# v1.net
KiCad netlist of a schematic drawn in EAGLE
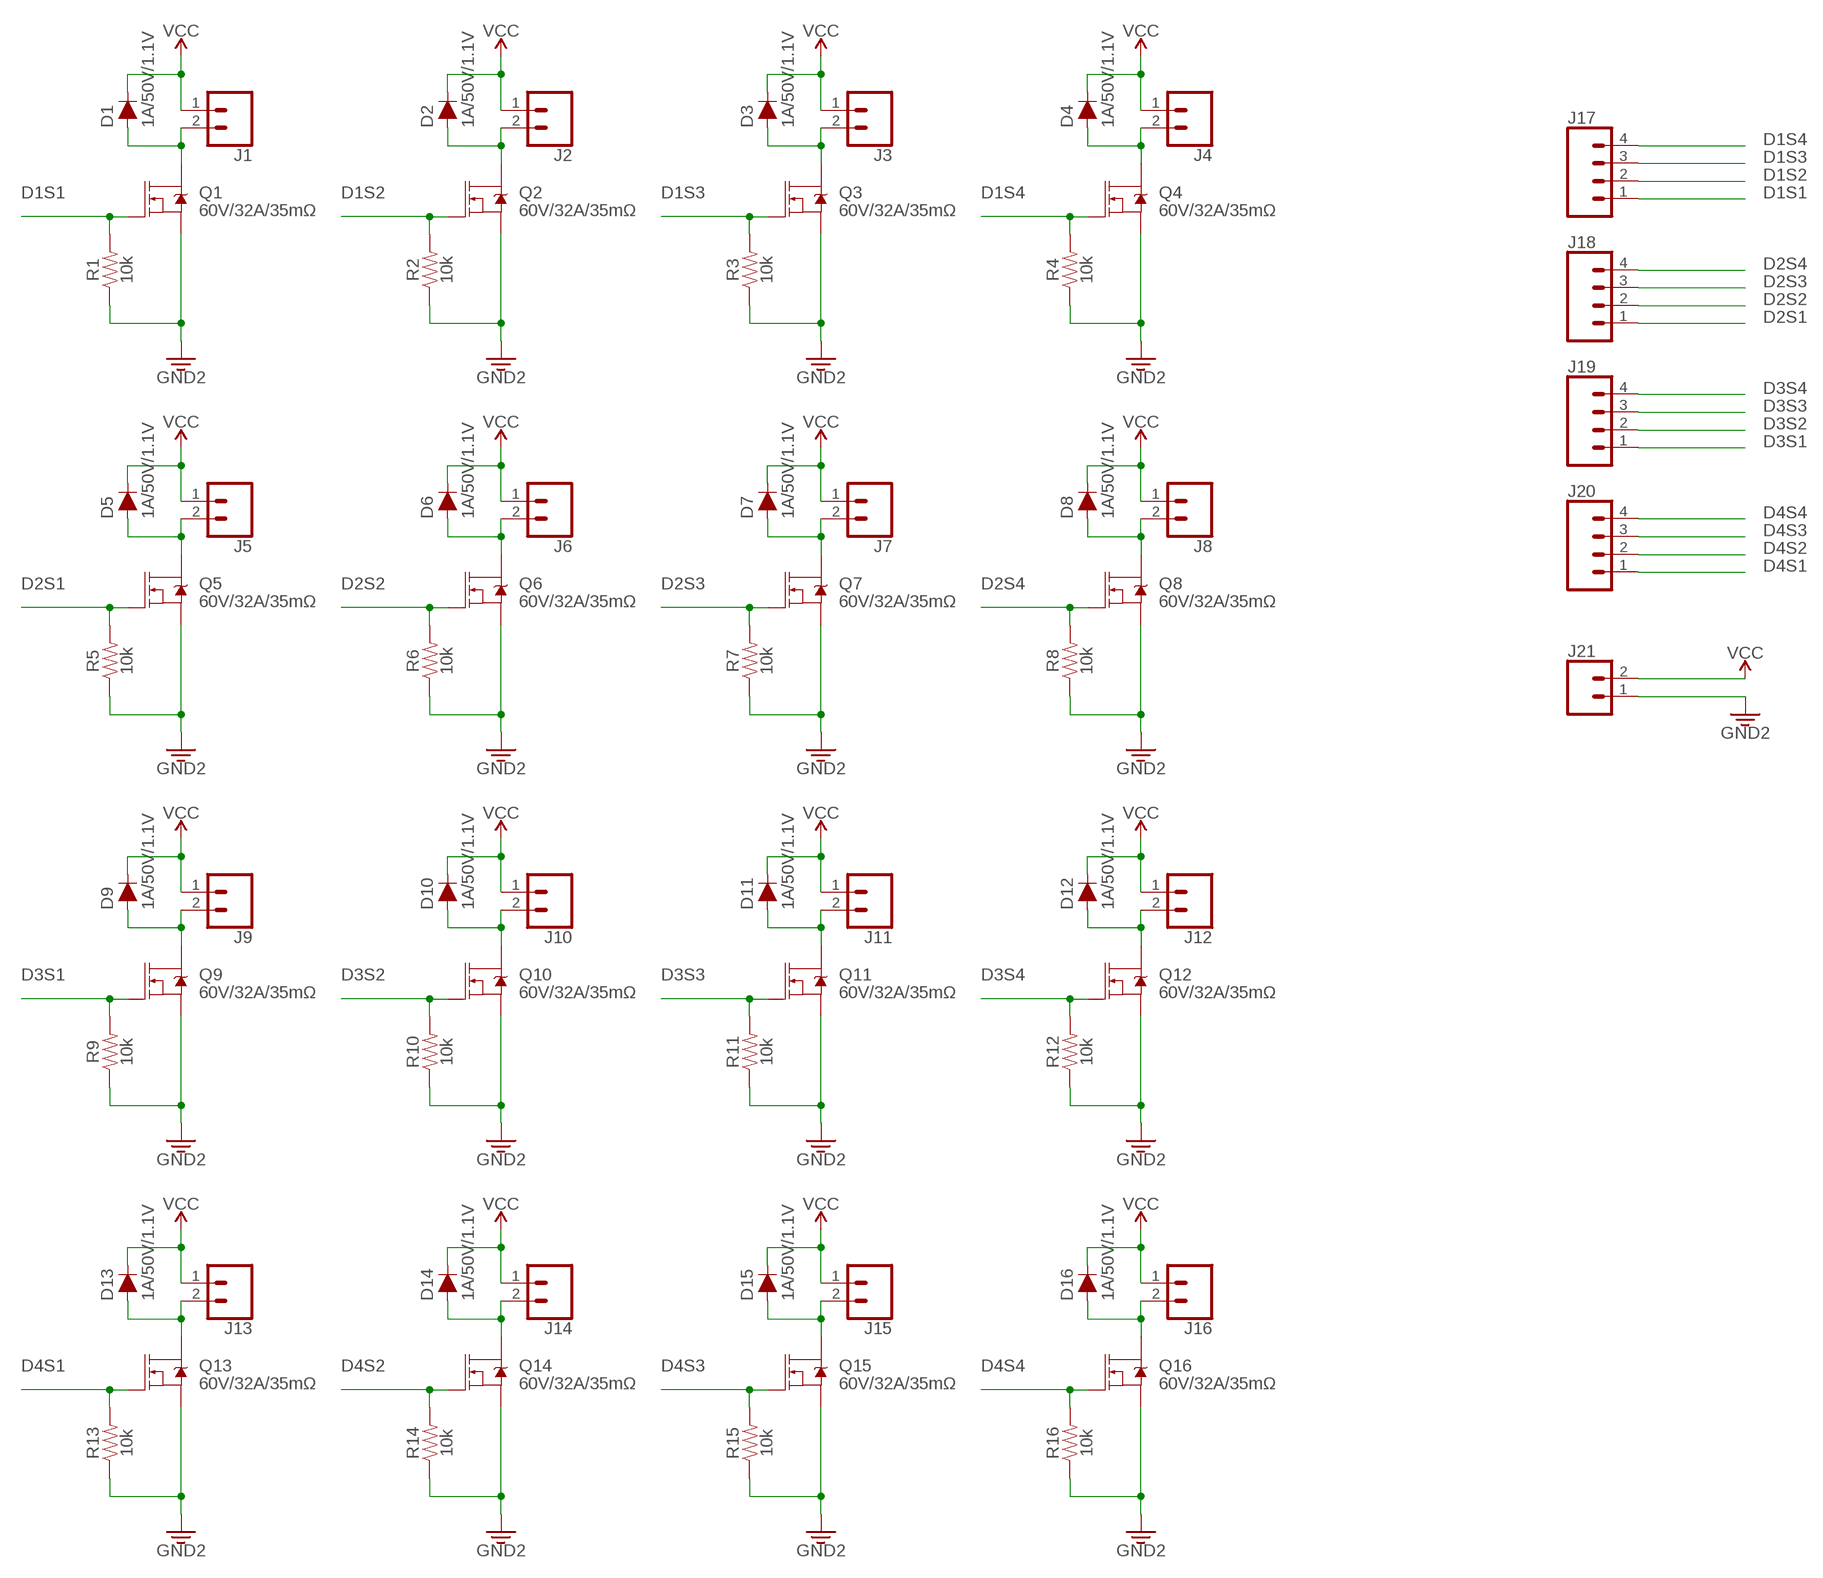
[diagram p0: schematic, sheet 1]

(export (version "E")
  (design (tool "Eeschema 10.0.6"))
  (components
    (comp (ref "D1")
      (value "1A/50V/1.1V")
      (footprint "eagle-import:DIODE-1N4001")
      (libsource (lib "eagle-import") (part "DIODE-PTH"))
    )
    (comp (ref "D2")
      (value "1A/50V/1.1V")
      (footprint "eagle-import:DIODE-1N4001")
      (libsource (lib "eagle-import") (part "DIODE-PTH"))
    )
    (comp (ref "D3")
      (value "1A/50V/1.1V")
      (footprint "eagle-import:DIODE-1N4001")
      (libsource (lib "eagle-import") (part "DIODE-PTH"))
    )
    (comp (ref "D4")
      (value "1A/50V/1.1V")
      (footprint "eagle-import:DIODE-1N4001")
      (libsource (lib "eagle-import") (part "DIODE-PTH"))
    )
    (comp (ref "D5")
      (value "1A/50V/1.1V")
      (footprint "eagle-import:DIODE-1N4001")
      (libsource (lib "eagle-import") (part "DIODE-PTH"))
    )
    (comp (ref "D6")
      (value "1A/50V/1.1V")
      (footprint "eagle-import:DIODE-1N4001")
      (libsource (lib "eagle-import") (part "DIODE-PTH"))
    )
    (comp (ref "D7")
      (value "1A/50V/1.1V")
      (footprint "eagle-import:DIODE-1N4001")
      (libsource (lib "eagle-import") (part "DIODE-PTH"))
    )
    (comp (ref "D8")
      (value "1A/50V/1.1V")
      (footprint "eagle-import:DIODE-1N4001")
      (libsource (lib "eagle-import") (part "DIODE-PTH"))
    )
    (comp (ref "D9")
      (value "1A/50V/1.1V")
      (footprint "eagle-import:DIODE-1N4001")
      (libsource (lib "eagle-import") (part "DIODE-PTH"))
    )
    (comp (ref "D10")
      (value "1A/50V/1.1V")
      (footprint "eagle-import:DIODE-1N4001")
      (libsource (lib "eagle-import") (part "DIODE-PTH"))
    )
    (comp (ref "D11")
      (value "1A/50V/1.1V")
      (footprint "eagle-import:DIODE-1N4001")
      (libsource (lib "eagle-import") (part "DIODE-PTH"))
    )
    (comp (ref "D12")
      (value "1A/50V/1.1V")
      (footprint "eagle-import:DIODE-1N4001")
      (libsource (lib "eagle-import") (part "DIODE-PTH"))
    )
    (comp (ref "D13")
      (value "1A/50V/1.1V")
      (footprint "eagle-import:DIODE-1N4001")
      (libsource (lib "eagle-import") (part "DIODE-PTH"))
    )
    (comp (ref "D14")
      (value "1A/50V/1.1V")
      (footprint "eagle-import:DIODE-1N4001")
      (libsource (lib "eagle-import") (part "DIODE-PTH"))
    )
    (comp (ref "D15")
      (value "1A/50V/1.1V")
      (footprint "eagle-import:DIODE-1N4001")
      (libsource (lib "eagle-import") (part "DIODE-PTH"))
    )
    (comp (ref "D16")
      (value "1A/50V/1.1V")
      (footprint "eagle-import:DIODE-1N4001")
      (libsource (lib "eagle-import") (part "DIODE-PTH"))
    )
    (comp (ref "J1")
      (value "CONN_02")
      (footprint "eagle-import:1X02")
      (libsource (lib "eagle-import") (part "CONN_02"))
    )
    (comp (ref "J2")
      (value "CONN_02")
      (footprint "eagle-import:1X02")
      (libsource (lib "eagle-import") (part "CONN_02"))
    )
    (comp (ref "J3")
      (value "CONN_02")
      (footprint "eagle-import:1X02")
      (libsource (lib "eagle-import") (part "CONN_02"))
    )
    (comp (ref "J4")
      (value "CONN_02")
      (footprint "eagle-import:1X02")
      (libsource (lib "eagle-import") (part "CONN_02"))
    )
    (comp (ref "J5")
      (value "CONN_02")
      (footprint "eagle-import:1X02")
      (libsource (lib "eagle-import") (part "CONN_02"))
    )
    (comp (ref "J6")
      (value "CONN_02")
      (footprint "eagle-import:1X02")
      (libsource (lib "eagle-import") (part "CONN_02"))
    )
    (comp (ref "J7")
      (value "CONN_02")
      (footprint "eagle-import:1X02")
      (libsource (lib "eagle-import") (part "CONN_02"))
    )
    (comp (ref "J8")
      (value "CONN_02")
      (footprint "eagle-import:1X02")
      (libsource (lib "eagle-import") (part "CONN_02"))
    )
    (comp (ref "J9")
      (value "CONN_02")
      (footprint "eagle-import:1X02")
      (libsource (lib "eagle-import") (part "CONN_02"))
    )
    (comp (ref "J10")
      (value "CONN_02")
      (footprint "eagle-import:1X02")
      (libsource (lib "eagle-import") (part "CONN_02"))
    )
    (comp (ref "J11")
      (value "CONN_02")
      (footprint "eagle-import:1X02")
      (libsource (lib "eagle-import") (part "CONN_02"))
    )
    (comp (ref "J12")
      (value "CONN_02")
      (footprint "eagle-import:1X02")
      (libsource (lib "eagle-import") (part "CONN_02"))
    )
    (comp (ref "J13")
      (value "CONN_02")
      (footprint "eagle-import:1X02")
      (libsource (lib "eagle-import") (part "CONN_02"))
    )
    (comp (ref "J14")
      (value "CONN_02")
      (footprint "eagle-import:1X02")
      (libsource (lib "eagle-import") (part "CONN_02"))
    )
    (comp (ref "J15")
      (value "CONN_02")
      (footprint "eagle-import:1X02")
      (libsource (lib "eagle-import") (part "CONN_02"))
    )
    (comp (ref "J16")
      (value "CONN_02")
      (footprint "eagle-import:1X02")
      (libsource (lib "eagle-import") (part "CONN_02"))
    )
    (comp (ref "J17")
      (value "CONN_04JST-PTH-VERT")
      (footprint "eagle-import:JST-4-PTH-VERT")
      (libsource (lib "eagle-import") (part "CONN_04JST-PTH-VERT"))
    )
    (comp (ref "J18")
      (value "CONN_04JST-PTH-VERT")
      (footprint "eagle-import:JST-4-PTH-VERT")
      (libsource (lib "eagle-import") (part "CONN_04JST-PTH-VERT"))
    )
    (comp (ref "J19")
      (value "CONN_04JST-PTH-VERT")
      (footprint "eagle-import:JST-4-PTH-VERT")
      (libsource (lib "eagle-import") (part "CONN_04JST-PTH-VERT"))
    )
    (comp (ref "J20")
      (value "CONN_04JST-PTH-VERT")
      (footprint "eagle-import:JST-4-PTH-VERT")
      (libsource (lib "eagle-import") (part "CONN_04JST-PTH-VERT"))
    )
    (comp (ref "J21")
      (value "CONN_025MM")
      (footprint "eagle-import:SCREWTERMINAL-5MM-2")
      (libsource (lib "eagle-import") (part "CONN_025MM"))
    )
    (comp (ref "Q1")
      (value "60V/32A/35mΩ")
      (footprint "eagle-import:TO220V")
      (libsource (lib "eagle-import") (part "MOSFET-NCH-FQP30N06L"))
    )
    (comp (ref "Q2")
      (value "60V/32A/35mΩ")
      (footprint "eagle-import:TO220V")
      (libsource (lib "eagle-import") (part "MOSFET-NCH-FQP30N06L"))
    )
    (comp (ref "Q3")
      (value "60V/32A/35mΩ")
      (footprint "eagle-import:TO220V")
      (libsource (lib "eagle-import") (part "MOSFET-NCH-FQP30N06L"))
    )
    (comp (ref "Q4")
      (value "60V/32A/35mΩ")
      (footprint "eagle-import:TO220V")
      (libsource (lib "eagle-import") (part "MOSFET-NCH-FQP30N06L"))
    )
    (comp (ref "Q5")
      (value "60V/32A/35mΩ")
      (footprint "eagle-import:TO220V")
      (libsource (lib "eagle-import") (part "MOSFET-NCH-FQP30N06L"))
    )
    (comp (ref "Q6")
      (value "60V/32A/35mΩ")
      (footprint "eagle-import:TO220V")
      (libsource (lib "eagle-import") (part "MOSFET-NCH-FQP30N06L"))
    )
    (comp (ref "Q7")
      (value "60V/32A/35mΩ")
      (footprint "eagle-import:TO220V")
      (libsource (lib "eagle-import") (part "MOSFET-NCH-FQP30N06L"))
    )
    (comp (ref "Q8")
      (value "60V/32A/35mΩ")
      (footprint "eagle-import:TO220V")
      (libsource (lib "eagle-import") (part "MOSFET-NCH-FQP30N06L"))
    )
    (comp (ref "Q9")
      (value "60V/32A/35mΩ")
      (footprint "eagle-import:TO220V")
      (libsource (lib "eagle-import") (part "MOSFET-NCH-FQP30N06L"))
    )
    (comp (ref "Q10")
      (value "60V/32A/35mΩ")
      (footprint "eagle-import:TO220V")
      (libsource (lib "eagle-import") (part "MOSFET-NCH-FQP30N06L"))
    )
    (comp (ref "Q11")
      (value "60V/32A/35mΩ")
      (footprint "eagle-import:TO220V")
      (libsource (lib "eagle-import") (part "MOSFET-NCH-FQP30N06L"))
    )
    (comp (ref "Q12")
      (value "60V/32A/35mΩ")
      (footprint "eagle-import:TO220V")
      (libsource (lib "eagle-import") (part "MOSFET-NCH-FQP30N06L"))
    )
    (comp (ref "Q13")
      (value "60V/32A/35mΩ")
      (footprint "eagle-import:TO220V")
      (libsource (lib "eagle-import") (part "MOSFET-NCH-FQP30N06L"))
    )
    (comp (ref "Q14")
      (value "60V/32A/35mΩ")
      (footprint "eagle-import:TO220V")
      (libsource (lib "eagle-import") (part "MOSFET-NCH-FQP30N06L"))
    )
    (comp (ref "Q15")
      (value "60V/32A/35mΩ")
      (footprint "eagle-import:TO220V")
      (libsource (lib "eagle-import") (part "MOSFET-NCH-FQP30N06L"))
    )
    (comp (ref "Q16")
      (value "60V/32A/35mΩ")
      (footprint "eagle-import:TO220V")
      (libsource (lib "eagle-import") (part "MOSFET-NCH-FQP30N06L"))
    )
    (comp (ref "R1")
      (value "10k")
      (footprint "eagle-import:AXIAL-0.3-KIT")
      (libsource (lib "eagle-import") (part "10KOHM-HORIZ_KIT-1/4W-5%"))
    )
    (comp (ref "R2")
      (value "10k")
      (footprint "eagle-import:AXIAL-0.3-KIT")
      (libsource (lib "eagle-import") (part "10KOHM-HORIZ_KIT-1/4W-5%"))
    )
    (comp (ref "R3")
      (value "10k")
      (footprint "eagle-import:AXIAL-0.3-KIT")
      (libsource (lib "eagle-import") (part "10KOHM-HORIZ_KIT-1/4W-5%"))
    )
    (comp (ref "R4")
      (value "10k")
      (footprint "eagle-import:AXIAL-0.3-KIT")
      (libsource (lib "eagle-import") (part "10KOHM-HORIZ_KIT-1/4W-5%"))
    )
    (comp (ref "R5")
      (value "10k")
      (footprint "eagle-import:AXIAL-0.3-KIT")
      (libsource (lib "eagle-import") (part "10KOHM-HORIZ_KIT-1/4W-5%"))
    )
    (comp (ref "R6")
      (value "10k")
      (footprint "eagle-import:AXIAL-0.3-KIT")
      (libsource (lib "eagle-import") (part "10KOHM-HORIZ_KIT-1/4W-5%"))
    )
    (comp (ref "R7")
      (value "10k")
      (footprint "eagle-import:AXIAL-0.3-KIT")
      (libsource (lib "eagle-import") (part "10KOHM-HORIZ_KIT-1/4W-5%"))
    )
    (comp (ref "R8")
      (value "10k")
      (footprint "eagle-import:AXIAL-0.3-KIT")
      (libsource (lib "eagle-import") (part "10KOHM-HORIZ_KIT-1/4W-5%"))
    )
    (comp (ref "R9")
      (value "10k")
      (footprint "eagle-import:AXIAL-0.3-KIT")
      (libsource (lib "eagle-import") (part "10KOHM-HORIZ_KIT-1/4W-5%"))
    )
    (comp (ref "R10")
      (value "10k")
      (footprint "eagle-import:AXIAL-0.3-KIT")
      (libsource (lib "eagle-import") (part "10KOHM-HORIZ_KIT-1/4W-5%"))
    )
    (comp (ref "R11")
      (value "10k")
      (footprint "eagle-import:AXIAL-0.3-KIT")
      (libsource (lib "eagle-import") (part "10KOHM-HORIZ_KIT-1/4W-5%"))
    )
    (comp (ref "R12")
      (value "10k")
      (footprint "eagle-import:AXIAL-0.3-KIT")
      (libsource (lib "eagle-import") (part "10KOHM-HORIZ_KIT-1/4W-5%"))
    )
    (comp (ref "R13")
      (value "10k")
      (footprint "eagle-import:AXIAL-0.3-KIT")
      (libsource (lib "eagle-import") (part "10KOHM-HORIZ_KIT-1/4W-5%"))
    )
    (comp (ref "R14")
      (value "10k")
      (footprint "eagle-import:AXIAL-0.3-KIT")
      (libsource (lib "eagle-import") (part "10KOHM-HORIZ_KIT-1/4W-5%"))
    )
    (comp (ref "R15")
      (value "10k")
      (footprint "eagle-import:AXIAL-0.3-KIT")
      (libsource (lib "eagle-import") (part "10KOHM-HORIZ_KIT-1/4W-5%"))
    )
    (comp (ref "R16")
      (value "10k")
      (footprint "eagle-import:AXIAL-0.3-KIT")
      (libsource (lib "eagle-import") (part "10KOHM-HORIZ_KIT-1/4W-5%"))
    )
  )
  (nets
    (net (code "1") (name "/D1S1") (class "Default")
      (node (ref "J17") (pin "1") (pinfunction "1_1") (pintype "passive"))
      (node (ref "Q1") (pin "1") (pinfunction "G_1") (pintype "bidirectional"))
      (node (ref "R1") (pin "P$2") (pinfunction "2_P$2") (pintype "passive"))
    )
    (net (code "2") (name "/D1S2") (class "Default")
      (node (ref "J17") (pin "2") (pinfunction "2_2") (pintype "passive"))
      (node (ref "Q2") (pin "1") (pinfunction "G_1") (pintype "bidirectional"))
      (node (ref "R2") (pin "P$2") (pinfunction "2_P$2") (pintype "passive"))
    )
    (net (code "3") (name "/D1S3") (class "Default")
      (node (ref "J17") (pin "3") (pinfunction "3_3") (pintype "passive"))
      (node (ref "Q3") (pin "1") (pinfunction "G_1") (pintype "bidirectional"))
      (node (ref "R3") (pin "P$2") (pinfunction "2_P$2") (pintype "passive"))
    )
    (net (code "4") (name "/D1S4") (class "Default")
      (node (ref "J17") (pin "4") (pinfunction "4_4") (pintype "passive"))
      (node (ref "Q4") (pin "1") (pinfunction "G_1") (pintype "bidirectional"))
      (node (ref "R4") (pin "P$2") (pinfunction "2_P$2") (pintype "passive"))
    )
    (net (code "5") (name "/D2S1") (class "Default")
      (node (ref "J18") (pin "1") (pinfunction "1_1") (pintype "passive"))
      (node (ref "Q5") (pin "1") (pinfunction "G_1") (pintype "bidirectional"))
      (node (ref "R5") (pin "P$2") (pinfunction "2_P$2") (pintype "passive"))
    )
    (net (code "6") (name "/D2S2") (class "Default")
      (node (ref "J18") (pin "2") (pinfunction "2_2") (pintype "passive"))
      (node (ref "Q6") (pin "1") (pinfunction "G_1") (pintype "bidirectional"))
      (node (ref "R6") (pin "P$2") (pinfunction "2_P$2") (pintype "passive"))
    )
    (net (code "7") (name "/D2S3") (class "Default")
      (node (ref "J18") (pin "3") (pinfunction "3_3") (pintype "passive"))
      (node (ref "Q7") (pin "1") (pinfunction "G_1") (pintype "bidirectional"))
      (node (ref "R7") (pin "P$2") (pinfunction "2_P$2") (pintype "passive"))
    )
    (net (code "8") (name "/D2S4") (class "Default")
      (node (ref "J18") (pin "4") (pinfunction "4_4") (pintype "passive"))
      (node (ref "Q8") (pin "1") (pinfunction "G_1") (pintype "bidirectional"))
      (node (ref "R8") (pin "P$2") (pinfunction "2_P$2") (pintype "passive"))
    )
    (net (code "9") (name "/D3S1") (class "Default")
      (node (ref "J19") (pin "1") (pinfunction "1_1") (pintype "passive"))
      (node (ref "Q9") (pin "1") (pinfunction "G_1") (pintype "bidirectional"))
      (node (ref "R9") (pin "P$2") (pinfunction "2_P$2") (pintype "passive"))
    )
    (net (code "10") (name "/D3S2") (class "Default")
      (node (ref "J19") (pin "2") (pinfunction "2_2") (pintype "passive"))
      (node (ref "Q10") (pin "1") (pinfunction "G_1") (pintype "bidirectional"))
      (node (ref "R10") (pin "P$2") (pinfunction "2_P$2") (pintype "passive"))
    )
    (net (code "11") (name "/D3S3") (class "Default")
      (node (ref "J19") (pin "3") (pinfunction "3_3") (pintype "passive"))
      (node (ref "Q11") (pin "1") (pinfunction "G_1") (pintype "bidirectional"))
      (node (ref "R11") (pin "P$2") (pinfunction "2_P$2") (pintype "passive"))
    )
    (net (code "12") (name "/D3S4") (class "Default")
      (node (ref "J19") (pin "4") (pinfunction "4_4") (pintype "passive"))
      (node (ref "Q12") (pin "1") (pinfunction "G_1") (pintype "bidirectional"))
      (node (ref "R12") (pin "P$2") (pinfunction "2_P$2") (pintype "passive"))
    )
    (net (code "13") (name "/D4S1") (class "Default")
      (node (ref "J20") (pin "1") (pinfunction "1_1") (pintype "passive"))
      (node (ref "Q13") (pin "1") (pinfunction "G_1") (pintype "bidirectional"))
      (node (ref "R13") (pin "P$2") (pinfunction "2_P$2") (pintype "passive"))
    )
    (net (code "14") (name "/D4S2") (class "Default")
      (node (ref "J20") (pin "2") (pinfunction "2_2") (pintype "passive"))
      (node (ref "Q14") (pin "1") (pinfunction "G_1") (pintype "bidirectional"))
      (node (ref "R14") (pin "P$2") (pinfunction "2_P$2") (pintype "passive"))
    )
    (net (code "15") (name "/D4S3") (class "Default")
      (node (ref "J20") (pin "3") (pinfunction "3_3") (pintype "passive"))
      (node (ref "Q15") (pin "1") (pinfunction "G_1") (pintype "bidirectional"))
      (node (ref "R15") (pin "P$2") (pinfunction "2_P$2") (pintype "passive"))
    )
    (net (code "16") (name "/D4S4") (class "Default")
      (node (ref "J20") (pin "4") (pinfunction "4_4") (pintype "passive"))
      (node (ref "Q16") (pin "1") (pinfunction "G_1") (pintype "bidirectional"))
      (node (ref "R16") (pin "P$2") (pinfunction "2_P$2") (pintype "passive"))
    )
    (net (code "17") (name "GND2") (class "Default")
      (node (ref "J21") (pin "1") (pinfunction "1_1") (pintype "passive"))
      (node (ref "Q1") (pin "3") (pinfunction "S_3") (pintype "bidirectional"))
      (node (ref "Q10") (pin "3") (pinfunction "S_3") (pintype "bidirectional"))
      (node (ref "Q11") (pin "3") (pinfunction "S_3") (pintype "bidirectional"))
      (node (ref "Q12") (pin "3") (pinfunction "S_3") (pintype "bidirectional"))
      (node (ref "Q13") (pin "3") (pinfunction "S_3") (pintype "bidirectional"))
      (node (ref "Q14") (pin "3") (pinfunction "S_3") (pintype "bidirectional"))
      (node (ref "Q15") (pin "3") (pinfunction "S_3") (pintype "bidirectional"))
      (node (ref "Q16") (pin "3") (pinfunction "S_3") (pintype "bidirectional"))
      (node (ref "Q2") (pin "3") (pinfunction "S_3") (pintype "bidirectional"))
      (node (ref "Q3") (pin "3") (pinfunction "S_3") (pintype "bidirectional"))
      (node (ref "Q4") (pin "3") (pinfunction "S_3") (pintype "bidirectional"))
      (node (ref "Q5") (pin "3") (pinfunction "S_3") (pintype "bidirectional"))
      (node (ref "Q6") (pin "3") (pinfunction "S_3") (pintype "bidirectional"))
      (node (ref "Q7") (pin "3") (pinfunction "S_3") (pintype "bidirectional"))
      (node (ref "Q8") (pin "3") (pinfunction "S_3") (pintype "bidirectional"))
      (node (ref "Q9") (pin "3") (pinfunction "S_3") (pintype "bidirectional"))
      (node (ref "R1") (pin "P$1") (pinfunction "1_P$1") (pintype "passive"))
      (node (ref "R10") (pin "P$1") (pinfunction "1_P$1") (pintype "passive"))
      (node (ref "R11") (pin "P$1") (pinfunction "1_P$1") (pintype "passive"))
      (node (ref "R12") (pin "P$1") (pinfunction "1_P$1") (pintype "passive"))
      (node (ref "R13") (pin "P$1") (pinfunction "1_P$1") (pintype "passive"))
      (node (ref "R14") (pin "P$1") (pinfunction "1_P$1") (pintype "passive"))
      (node (ref "R15") (pin "P$1") (pinfunction "1_P$1") (pintype "passive"))
      (node (ref "R16") (pin "P$1") (pinfunction "1_P$1") (pintype "passive"))
      (node (ref "R2") (pin "P$1") (pinfunction "1_P$1") (pintype "passive"))
      (node (ref "R3") (pin "P$1") (pinfunction "1_P$1") (pintype "passive"))
      (node (ref "R4") (pin "P$1") (pinfunction "1_P$1") (pintype "passive"))
      (node (ref "R5") (pin "P$1") (pinfunction "1_P$1") (pintype "passive"))
      (node (ref "R6") (pin "P$1") (pinfunction "1_P$1") (pintype "passive"))
      (node (ref "R7") (pin "P$1") (pinfunction "1_P$1") (pintype "passive"))
      (node (ref "R8") (pin "P$1") (pinfunction "1_P$1") (pintype "passive"))
      (node (ref "R9") (pin "P$1") (pinfunction "1_P$1") (pintype "passive"))
    )
    (net (code "18") (name "Net-(Q1-D)") (class "Default")
      (node (ref "D1") (pin "A") (pinfunction "A_A") (pintype "passive"))
      (node (ref "J1") (pin "2") (pinfunction "2_2") (pintype "passive"))
      (node (ref "Q1") (pin "2") (pinfunction "D_2") (pintype "bidirectional"))
    )
    (net (code "19") (name "Net-(Q2-D)") (class "Default")
      (node (ref "D2") (pin "A") (pinfunction "A_A") (pintype "passive"))
      (node (ref "J2") (pin "2") (pinfunction "2_2") (pintype "passive"))
      (node (ref "Q2") (pin "2") (pinfunction "D_2") (pintype "bidirectional"))
    )
    (net (code "20") (name "Net-(Q3-D)") (class "Default")
      (node (ref "D3") (pin "A") (pinfunction "A_A") (pintype "passive"))
      (node (ref "J3") (pin "2") (pinfunction "2_2") (pintype "passive"))
      (node (ref "Q3") (pin "2") (pinfunction "D_2") (pintype "bidirectional"))
    )
    (net (code "21") (name "Net-(Q4-D)") (class "Default")
      (node (ref "D4") (pin "A") (pinfunction "A_A") (pintype "passive"))
      (node (ref "J4") (pin "2") (pinfunction "2_2") (pintype "passive"))
      (node (ref "Q4") (pin "2") (pinfunction "D_2") (pintype "bidirectional"))
    )
    (net (code "22") (name "Net-(Q5-D)") (class "Default")
      (node (ref "D5") (pin "A") (pinfunction "A_A") (pintype "passive"))
      (node (ref "J5") (pin "2") (pinfunction "2_2") (pintype "passive"))
      (node (ref "Q5") (pin "2") (pinfunction "D_2") (pintype "bidirectional"))
    )
    (net (code "23") (name "Net-(Q6-D)") (class "Default")
      (node (ref "D6") (pin "A") (pinfunction "A_A") (pintype "passive"))
      (node (ref "J6") (pin "2") (pinfunction "2_2") (pintype "passive"))
      (node (ref "Q6") (pin "2") (pinfunction "D_2") (pintype "bidirectional"))
    )
    (net (code "24") (name "Net-(Q7-D)") (class "Default")
      (node (ref "D7") (pin "A") (pinfunction "A_A") (pintype "passive"))
      (node (ref "J7") (pin "2") (pinfunction "2_2") (pintype "passive"))
      (node (ref "Q7") (pin "2") (pinfunction "D_2") (pintype "bidirectional"))
    )
    (net (code "25") (name "Net-(Q8-D)") (class "Default")
      (node (ref "D8") (pin "A") (pinfunction "A_A") (pintype "passive"))
      (node (ref "J8") (pin "2") (pinfunction "2_2") (pintype "passive"))
      (node (ref "Q8") (pin "2") (pinfunction "D_2") (pintype "bidirectional"))
    )
    (net (code "26") (name "Net-(Q9-D)") (class "Default")
      (node (ref "D9") (pin "A") (pinfunction "A_A") (pintype "passive"))
      (node (ref "J9") (pin "2") (pinfunction "2_2") (pintype "passive"))
      (node (ref "Q9") (pin "2") (pinfunction "D_2") (pintype "bidirectional"))
    )
    (net (code "27") (name "Net-(Q10-D)") (class "Default")
      (node (ref "D10") (pin "A") (pinfunction "A_A") (pintype "passive"))
      (node (ref "J10") (pin "2") (pinfunction "2_2") (pintype "passive"))
      (node (ref "Q10") (pin "2") (pinfunction "D_2") (pintype "bidirectional"))
    )
    (net (code "28") (name "Net-(Q11-D)") (class "Default")
      (node (ref "D11") (pin "A") (pinfunction "A_A") (pintype "passive"))
      (node (ref "J11") (pin "2") (pinfunction "2_2") (pintype "passive"))
      (node (ref "Q11") (pin "2") (pinfunction "D_2") (pintype "bidirectional"))
    )
    (net (code "29") (name "Net-(Q12-D)") (class "Default")
      (node (ref "D12") (pin "A") (pinfunction "A_A") (pintype "passive"))
      (node (ref "J12") (pin "2") (pinfunction "2_2") (pintype "passive"))
      (node (ref "Q12") (pin "2") (pinfunction "D_2") (pintype "bidirectional"))
    )
    (net (code "30") (name "Net-(Q13-D)") (class "Default")
      (node (ref "D13") (pin "A") (pinfunction "A_A") (pintype "passive"))
      (node (ref "J13") (pin "2") (pinfunction "2_2") (pintype "passive"))
      (node (ref "Q13") (pin "2") (pinfunction "D_2") (pintype "bidirectional"))
    )
    (net (code "31") (name "Net-(Q14-D)") (class "Default")
      (node (ref "D14") (pin "A") (pinfunction "A_A") (pintype "passive"))
      (node (ref "J14") (pin "2") (pinfunction "2_2") (pintype "passive"))
      (node (ref "Q14") (pin "2") (pinfunction "D_2") (pintype "bidirectional"))
    )
    (net (code "32") (name "Net-(Q15-D)") (class "Default")
      (node (ref "D15") (pin "A") (pinfunction "A_A") (pintype "passive"))
      (node (ref "J15") (pin "2") (pinfunction "2_2") (pintype "passive"))
      (node (ref "Q15") (pin "2") (pinfunction "D_2") (pintype "bidirectional"))
    )
    (net (code "33") (name "Net-(Q16-D)") (class "Default")
      (node (ref "D16") (pin "A") (pinfunction "A_A") (pintype "passive"))
      (node (ref "J16") (pin "2") (pinfunction "2_2") (pintype "passive"))
      (node (ref "Q16") (pin "2") (pinfunction "D_2") (pintype "bidirectional"))
    )
    (net (code "34") (name "VCC") (class "Default")
      (node (ref "D1") (pin "C") (pinfunction "C_C") (pintype "passive"))
      (node (ref "D10") (pin "C") (pinfunction "C_C") (pintype "passive"))
      (node (ref "D11") (pin "C") (pinfunction "C_C") (pintype "passive"))
      (node (ref "D12") (pin "C") (pinfunction "C_C") (pintype "passive"))
      (node (ref "D13") (pin "C") (pinfunction "C_C") (pintype "passive"))
      (node (ref "D14") (pin "C") (pinfunction "C_C") (pintype "passive"))
      (node (ref "D15") (pin "C") (pinfunction "C_C") (pintype "passive"))
      (node (ref "D16") (pin "C") (pinfunction "C_C") (pintype "passive"))
      (node (ref "D2") (pin "C") (pinfunction "C_C") (pintype "passive"))
      (node (ref "D3") (pin "C") (pinfunction "C_C") (pintype "passive"))
      (node (ref "D4") (pin "C") (pinfunction "C_C") (pintype "passive"))
      (node (ref "D5") (pin "C") (pinfunction "C_C") (pintype "passive"))
      (node (ref "D6") (pin "C") (pinfunction "C_C") (pintype "passive"))
      (node (ref "D7") (pin "C") (pinfunction "C_C") (pintype "passive"))
      (node (ref "D8") (pin "C") (pinfunction "C_C") (pintype "passive"))
      (node (ref "D9") (pin "C") (pinfunction "C_C") (pintype "passive"))
      (node (ref "J1") (pin "1") (pinfunction "1_1") (pintype "passive"))
      (node (ref "J10") (pin "1") (pinfunction "1_1") (pintype "passive"))
      (node (ref "J11") (pin "1") (pinfunction "1_1") (pintype "passive"))
      (node (ref "J12") (pin "1") (pinfunction "1_1") (pintype "passive"))
      (node (ref "J13") (pin "1") (pinfunction "1_1") (pintype "passive"))
      (node (ref "J14") (pin "1") (pinfunction "1_1") (pintype "passive"))
      (node (ref "J15") (pin "1") (pinfunction "1_1") (pintype "passive"))
      (node (ref "J16") (pin "1") (pinfunction "1_1") (pintype "passive"))
      (node (ref "J2") (pin "1") (pinfunction "1_1") (pintype "passive"))
      (node (ref "J21") (pin "2") (pinfunction "2_2") (pintype "passive"))
      (node (ref "J3") (pin "1") (pinfunction "1_1") (pintype "passive"))
      (node (ref "J4") (pin "1") (pinfunction "1_1") (pintype "passive"))
      (node (ref "J5") (pin "1") (pinfunction "1_1") (pintype "passive"))
      (node (ref "J6") (pin "1") (pinfunction "1_1") (pintype "passive"))
      (node (ref "J7") (pin "1") (pinfunction "1_1") (pintype "passive"))
      (node (ref "J8") (pin "1") (pinfunction "1_1") (pintype "passive"))
      (node (ref "J9") (pin "1") (pinfunction "1_1") (pintype "passive"))
    )
  )
)
